# zigbee-dimmer.net
KiCad netlist of a schematic drawn in EAGLE
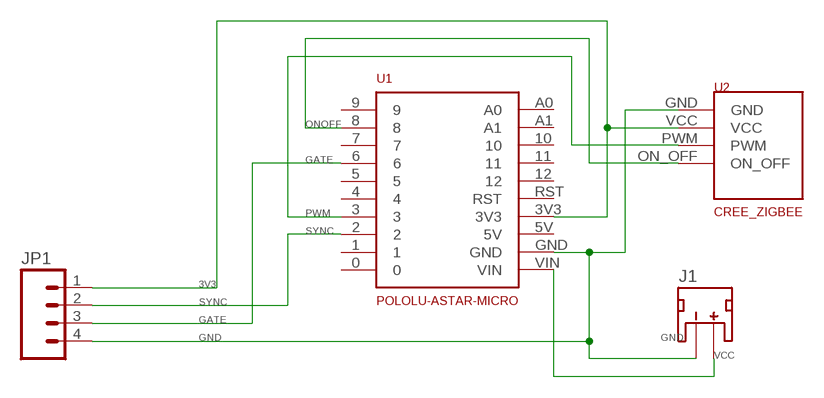
[diagram p0: schematic, sheet 1]

(export (version "E")
  (design (tool "Eeschema 10.0.6"))
  (components
    (comp (ref "J1")
      (value "JST_2MM_MALE")
      (footprint "eagle-import:JST-2-SMD")
      (libsource (lib "eagle-import") (part "JST_2MM_MALE"))
    )
    (comp (ref "JP1")
      (value "DIMMER_PINSSMD_180")
      (footprint "eagle-import:1X04-SMD")
      (libsource (lib "eagle-import") (part "DIMMER_PINSSMD_180"))
    )
    (comp (ref "U1")
      (value "POLOLU-ASTAR-MICRO")
      (footprint "eagle-import:POLOLU-ASTAR-MICRO")
      (libsource (lib "eagle-import") (part "POLOLU-ASTAR-MICRO"))
    )
    (comp (ref "U2")
      (value "CREE_ZIGBEE")
      (footprint "eagle-import:CREE-ZIGBEE")
      (libsource (lib "eagle-import") (part "CREE_ZIGBEE"))
    )
  )
  (nets
    (net (code "1") (name "/3V3") (class "Default")
      (node (ref "JP1") (pin "1") (pinfunction "4_1") (pintype "passive"))
      (node (ref "U1") (pin "3V3") (pinfunction "3V3_3V3") (pintype "power_in"))
      (node (ref "U2") (pin "VCC") (pinfunction "VCC_VCC") (pintype "power_in"))
    )
    (net (code "2") (name "/5V") (class "Default")
      (node (ref "U1") (pin "5V") (pinfunction "5V_5V") (pintype "power_in"))
    )
    (net (code "3") (name "/GATE") (class "Default")
      (node (ref "JP1") (pin "3") (pinfunction "2_3") (pintype "passive"))
      (node (ref "U1") (pin "6") (pinfunction "6_6") (pintype "bidirectional"))
    )
    (net (code "4") (name "/GND") (class "Default")
      (node (ref "J1") (pin "1") (pinfunction "-_1") (pintype "bidirectional"))
      (node (ref "JP1") (pin "4") (pinfunction "1_4") (pintype "passive"))
      (node (ref "U1") (pin "GND") (pinfunction "GND_GND") (pintype "power_in"))
      (node (ref "U2") (pin "GND") (pinfunction "GND_GND") (pintype "power_in"))
    )
    (net (code "5") (name "/ONOFF") (class "Default")
      (node (ref "U1") (pin "8") (pinfunction "8_8") (pintype "bidirectional"))
      (node (ref "U2") (pin "ON_OFF") (pinfunction "ON_OFF_ON_OFF") (pintype "bidirectional"))
    )
    (net (code "6") (name "/PWM") (class "Default")
      (node (ref "U1") (pin "3") (pinfunction "3_3") (pintype "bidirectional"))
      (node (ref "U2") (pin "PWM") (pinfunction "PWM_PWM") (pintype "bidirectional"))
    )
    (net (code "7") (name "/SYNC") (class "Default")
      (node (ref "JP1") (pin "2") (pinfunction "3_2") (pintype "passive"))
      (node (ref "U1") (pin "2") (pinfunction "2_2") (pintype "bidirectional"))
    )
    (net (code "8") (name "/VCC") (class "Default")
      (node (ref "J1") (pin "2") (pinfunction "+_2") (pintype "bidirectional"))
      (node (ref "U1") (pin "VIN") (pinfunction "VIN_VIN") (pintype "power_in"))
    )
    (net (code "9") (name "unconnected-(J1-PAD1-PadNC1)") (class "Default")
      (node (ref "J1") (pin "NC1") (pinfunction "PAD1_NC1") (pintype "bidirectional"))
    )
    (net (code "10") (name "unconnected-(J1-PAD2-PadNC2)") (class "Default")
      (node (ref "J1") (pin "NC2") (pinfunction "PAD2_NC2") (pintype "bidirectional"))
    )
    (net (code "11") (name "unconnected-(U1-Pad0)") (class "Default")
      (node (ref "U1") (pin "0") (pinfunction "0_0") (pintype "bidirectional"))
    )
    (net (code "12") (name "unconnected-(U1-Pad1)") (class "Default")
      (node (ref "U1") (pin "1") (pinfunction "1_1") (pintype "bidirectional"))
    )
    (net (code "13") (name "unconnected-(U1-Pad4)") (class "Default")
      (node (ref "U1") (pin "4") (pinfunction "4_4") (pintype "bidirectional"))
    )
    (net (code "14") (name "unconnected-(U1-Pad5)") (class "Default")
      (node (ref "U1") (pin "5") (pinfunction "5_5") (pintype "bidirectional"))
    )
    (net (code "15") (name "unconnected-(U1-Pad7)") (class "Default")
      (node (ref "U1") (pin "7") (pinfunction "7_7") (pintype "bidirectional"))
    )
    (net (code "16") (name "unconnected-(U1-Pad9)") (class "Default")
      (node (ref "U1") (pin "9") (pinfunction "9_9") (pintype "bidirectional"))
    )
    (net (code "17") (name "unconnected-(U1-Pad10)") (class "Default")
      (node (ref "U1") (pin "10") (pinfunction "10_10") (pintype "bidirectional"))
    )
    (net (code "18") (name "unconnected-(U1-Pad11)") (class "Default")
      (node (ref "U1") (pin "11") (pinfunction "11_11") (pintype "bidirectional"))
    )
    (net (code "19") (name "unconnected-(U1-Pad12)") (class "Default")
      (node (ref "U1") (pin "12") (pinfunction "12_12") (pintype "bidirectional"))
    )
    (net (code "20") (name "unconnected-(U1-PadA0)") (class "Default")
      (node (ref "U1") (pin "A0") (pinfunction "A0_A0") (pintype "bidirectional"))
    )
    (net (code "21") (name "unconnected-(U1-PadA1)") (class "Default")
      (node (ref "U1") (pin "A1") (pinfunction "A1_A1") (pintype "bidirectional"))
    )
    (net (code "22") (name "unconnected-(U1-PadRST)") (class "Default")
      (node (ref "U1") (pin "RST") (pinfunction "RST_RST") (pintype "input"))
    )
  )
)
